# zumo_V1_FABRICATED_enc_only.net
KiCad netlist of a schematic drawn in EAGLE
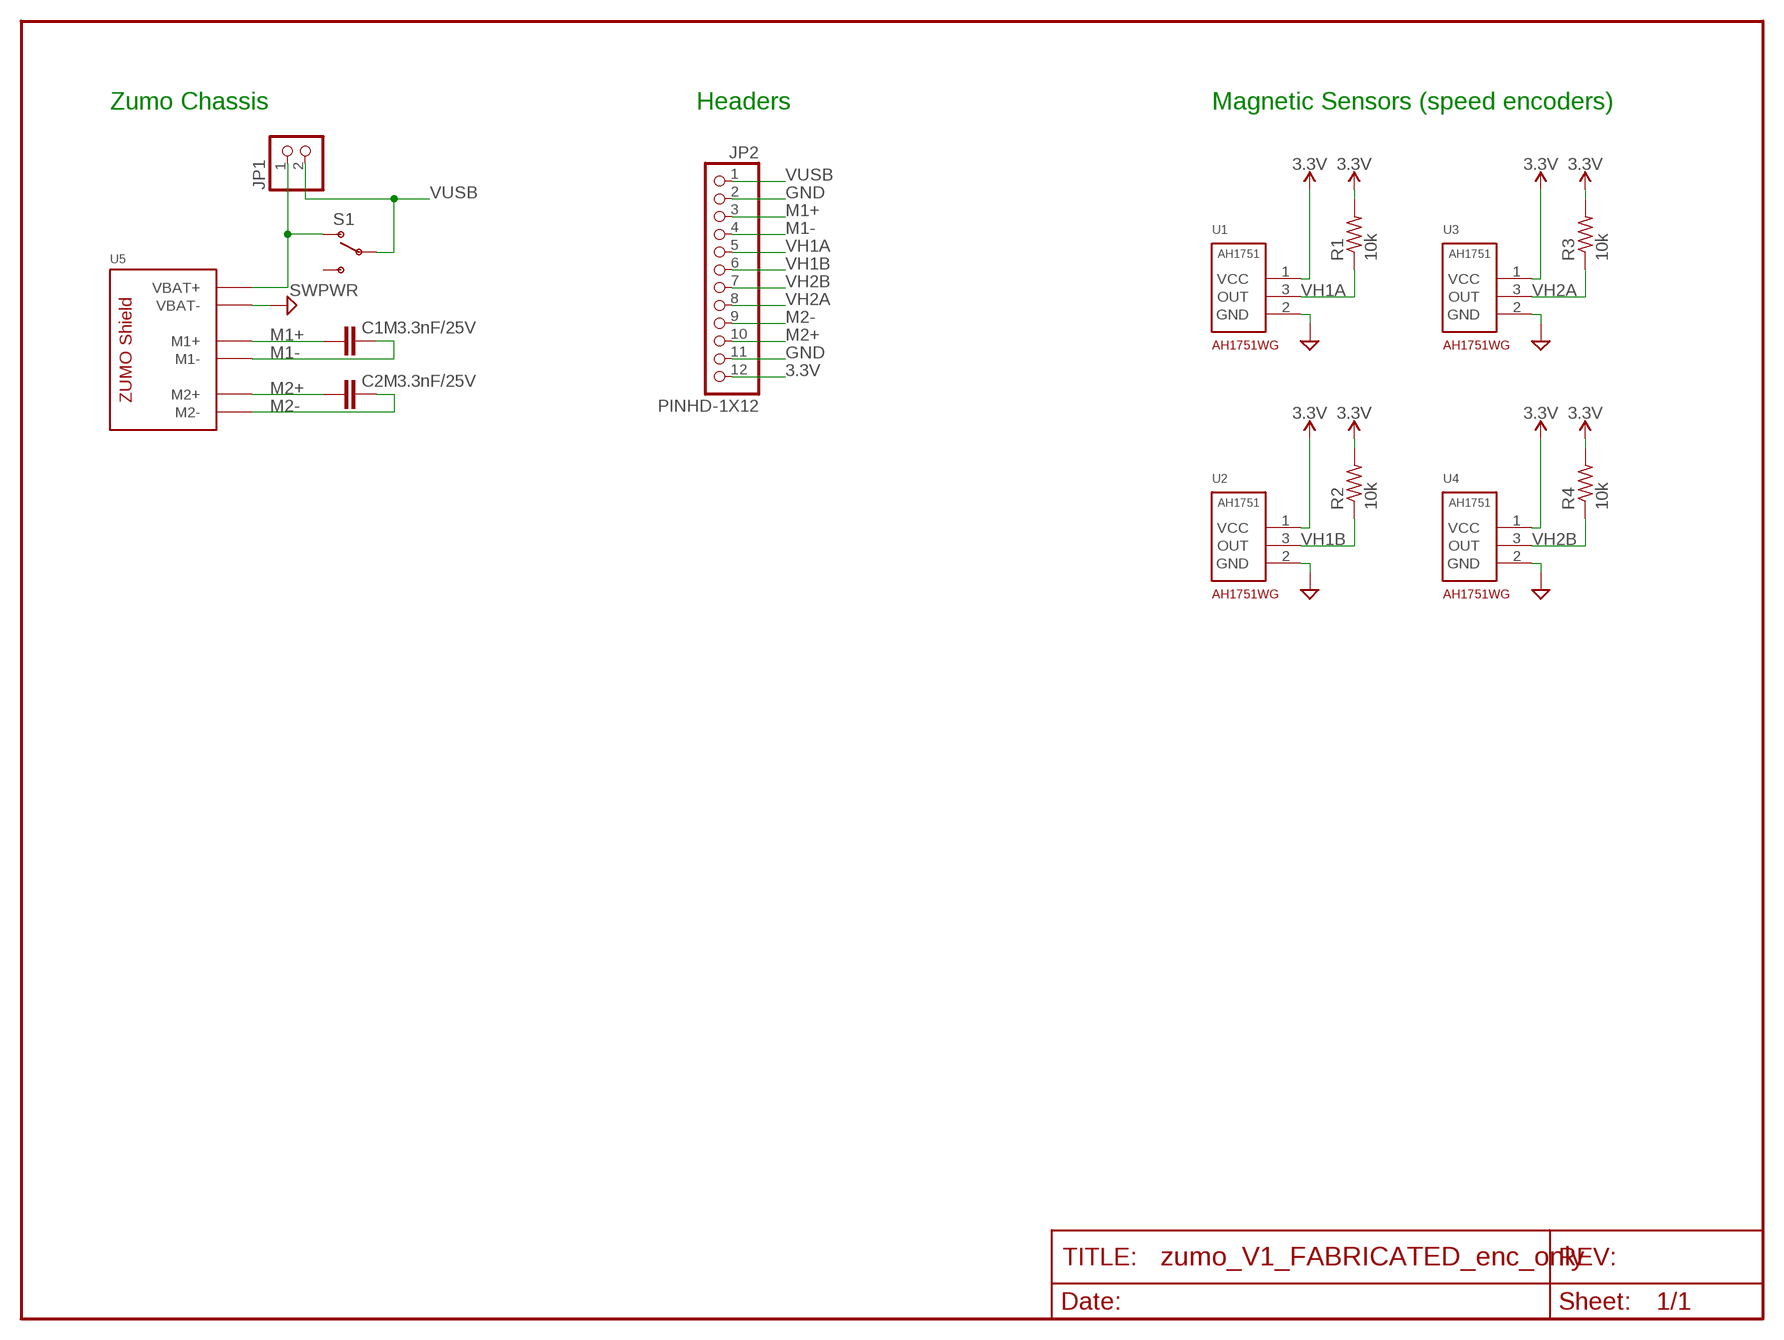
[diagram p0: schematic, sheet 1]

(export (version "E")
  (design (tool "Eeschema 10.0.6"))
  (components
    (comp (ref "C1M")
      (value "3.3nF/25V")
      (footprint "eagle-import:C0805")
      (libsource (lib "eagle-import") (part "CAPACITORC0805"))
    )
    (comp (ref "C2M")
      (value "3.3nF/25V")
      (footprint "eagle-import:C0805")
      (libsource (lib "eagle-import") (part "CAPACITORC0805"))
    )
    (comp (ref "JP1")
      (value "JPWR")
      (footprint "eagle-import:1X02")
      (libsource (lib "eagle-import") (part "PINHD-1X2"))
    )
    (comp (ref "JP2")
      (value "PINHD-1X12")
      (footprint "eagle-import:1X12")
      (libsource (lib "eagle-import") (part "PINHD-1X12"))
    )
    (comp (ref "R1")
      (value "10k")
      (footprint "eagle-import:R0805")
      (libsource (lib "eagle-import") (part "RESISTORR0805"))
    )
    (comp (ref "R2")
      (value "10k")
      (footprint "eagle-import:R0805")
      (libsource (lib "eagle-import") (part "RESISTORR0805"))
    )
    (comp (ref "R3")
      (value "10k")
      (footprint "eagle-import:R0805")
      (libsource (lib "eagle-import") (part "RESISTORR0805"))
    )
    (comp (ref "R4")
      (value "10k")
      (footprint "eagle-import:R0805")
      (libsource (lib "eagle-import") (part "RESISTORR0805"))
    )
    (comp (ref "S1")
      (value "SWPWR")
      (footprint "eagle-import:AYZ0202")
      (fields (field (name "DIGIKEY") "401-2013-6-ND"))
      (libsource (lib "eagle-import") (part "SWITCH-SPSTSMD"))
    )
    (comp (ref "U1")
      (value "AH1751WG")
      (footprint "eagle-import:SC59")
      (libsource (lib "eagle-import") (part "AH1751WG"))
    )
    (comp (ref "U2")
      (value "AH1751WG")
      (footprint "eagle-import:SC59")
      (libsource (lib "eagle-import") (part "AH1751WG"))
    )
    (comp (ref "U3")
      (value "AH1751WG")
      (footprint "eagle-import:SC59")
      (libsource (lib "eagle-import") (part "AH1751WG"))
    )
    (comp (ref "U4")
      (value "AH1751WG")
      (footprint "eagle-import:SC59")
      (libsource (lib "eagle-import") (part "AH1751WG"))
    )
    (comp (ref "U5")
      (value "ZUMONO_TABS")
      (footprint "eagle-import:ZUMO_NO_TABS")
      (libsource (lib "eagle-import") (part "ZUMONO_TABS"))
    )
  )
  (nets
    (net (code "1") (name "/M1+") (class "Default")
      (node (ref "C1M") (pin "2") (pinfunction "2_2") (pintype "passive"))
      (node (ref "JP2") (pin "3") (pinfunction "3_3") (pintype "passive"))
      (node (ref "U5") (pin "M1+") (pinfunction "M1+_M1+") (pintype "bidirectional"))
    )
    (net (code "2") (name "/M1-") (class "Default")
      (node (ref "C1M") (pin "1") (pinfunction "1_1") (pintype "passive"))
      (node (ref "JP2") (pin "4") (pinfunction "4_4") (pintype "passive"))
      (node (ref "U5") (pin "M1-") (pinfunction "M1-_M1-") (pintype "bidirectional"))
    )
    (net (code "3") (name "/M2+") (class "Default")
      (node (ref "C2M") (pin "2") (pinfunction "2_2") (pintype "passive"))
      (node (ref "JP2") (pin "10") (pinfunction "10_10") (pintype "passive"))
      (node (ref "U5") (pin "M2+") (pinfunction "M2+_M2+") (pintype "bidirectional"))
    )
    (net (code "4") (name "/M2-") (class "Default")
      (node (ref "C2M") (pin "1") (pinfunction "1_1") (pintype "passive"))
      (node (ref "JP2") (pin "9") (pinfunction "9_9") (pintype "passive"))
      (node (ref "U5") (pin "M2-") (pinfunction "M2-_M2-") (pintype "bidirectional"))
    )
    (net (code "5") (name "/VH1A") (class "Default")
      (node (ref "JP2") (pin "5") (pinfunction "5_5") (pintype "passive"))
      (node (ref "R1") (pin "1") (pinfunction "1_1") (pintype "passive"))
      (node (ref "U1") (pin "3") (pinfunction "OUT_3") (pintype "bidirectional"))
    )
    (net (code "6") (name "/VH1B") (class "Default")
      (node (ref "JP2") (pin "6") (pinfunction "6_6") (pintype "passive"))
      (node (ref "R2") (pin "1") (pinfunction "1_1") (pintype "passive"))
      (node (ref "U2") (pin "3") (pinfunction "OUT_3") (pintype "bidirectional"))
    )
    (net (code "7") (name "/VH2A") (class "Default")
      (node (ref "JP2") (pin "8") (pinfunction "8_8") (pintype "passive"))
      (node (ref "R3") (pin "1") (pinfunction "1_1") (pintype "passive"))
      (node (ref "U3") (pin "3") (pinfunction "OUT_3") (pintype "bidirectional"))
    )
    (net (code "8") (name "/VH2B") (class "Default")
      (node (ref "JP2") (pin "7") (pinfunction "7_7") (pintype "passive"))
      (node (ref "R4") (pin "1") (pinfunction "1_1") (pintype "passive"))
      (node (ref "U4") (pin "3") (pinfunction "OUT_3") (pintype "bidirectional"))
    )
    (net (code "9") (name "/VUSB") (class "Default")
      (node (ref "JP1") (pin "2") (pinfunction "2_2") (pintype "passive"))
      (node (ref "JP2") (pin "1") (pinfunction "1_1") (pintype "passive"))
      (node (ref "S1") (pin "2") (pinfunction "P_2") (pintype "passive"))
    )
    (net (code "10") (name "3.3V") (class "Default")
      (node (ref "JP2") (pin "12") (pinfunction "12_12") (pintype "passive"))
      (node (ref "R1") (pin "2") (pinfunction "2_2") (pintype "passive"))
      (node (ref "R2") (pin "2") (pinfunction "2_2") (pintype "passive"))
      (node (ref "R3") (pin "2") (pinfunction "2_2") (pintype "passive"))
      (node (ref "R4") (pin "2") (pinfunction "2_2") (pintype "passive"))
      (node (ref "U1") (pin "1") (pinfunction "VCC_1") (pintype "bidirectional"))
      (node (ref "U2") (pin "1") (pinfunction "VCC_1") (pintype "bidirectional"))
      (node (ref "U3") (pin "1") (pinfunction "VCC_1") (pintype "bidirectional"))
      (node (ref "U4") (pin "1") (pinfunction "VCC_1") (pintype "bidirectional"))
    )
    (net (code "11") (name "GND") (class "Default")
      (node (ref "JP2") (pin "11") (pinfunction "11_11") (pintype "passive"))
      (node (ref "JP2") (pin "2") (pinfunction "2_2") (pintype "passive"))
      (node (ref "U1") (pin "2") (pinfunction "GND_2") (pintype "power_in"))
      (node (ref "U2") (pin "2") (pinfunction "GND_2") (pintype "power_in"))
      (node (ref "U3") (pin "2") (pinfunction "GND_2") (pintype "power_in"))
      (node (ref "U4") (pin "2") (pinfunction "GND_2") (pintype "power_in"))
      (node (ref "U5") (pin "VBAT-") (pinfunction "VBAT-_VBAT-") (pintype "bidirectional"))
    )
    (net (code "12") (name "Net-(S1-O)") (class "Default")
      (node (ref "JP1") (pin "1") (pinfunction "1_1") (pintype "passive"))
      (node (ref "S1") (pin "1") (pinfunction "O_1") (pintype "passive"))
      (node (ref "U5") (pin "VBAT+") (pinfunction "VBAT+_VBAT+") (pintype "bidirectional"))
    )
    (net (code "13") (name "unconnected-(S1-S-Pad3)") (class "Default")
      (node (ref "S1") (pin "3") (pinfunction "S_3") (pintype "passive"))
    )
  )
)
